# LAN8720.net
KiCad netlist of a schematic drawn in Altium Designer
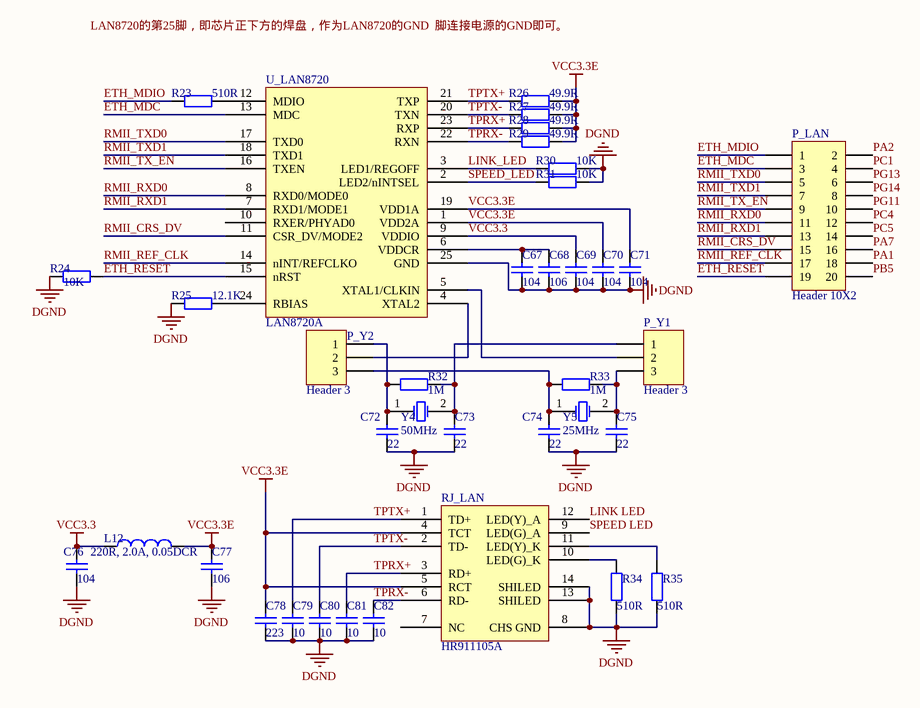
[diagram p0: LAN8720.SchDoc]

(export (version "E")
  (design (tool "Eeschema 10.0.6"))
  (components
    (comp (ref "C67")
      (value "104")
      (footprint "SMT-0603")
      (description "Capacitor")
      (fields (field (name "Comment") "Cap") (field (name "PUBLISHER") "Altium Limited"))
      (libsource (lib "Miscellaneous Devices") (part "Cap"))
    )
    (comp (ref "C68")
      (value "106")
      (footprint "SMT-0603")
      (description "Capacitor")
      (fields (field (name "Comment") "Cap") (field (name "PUBLISHER") "Altium Limited"))
      (libsource (lib "Miscellaneous Devices") (part "Cap"))
    )
    (comp (ref "C69")
      (value "104")
      (footprint "SMT-0603")
      (description "Capacitor")
      (fields (field (name "Comment") "Cap") (field (name "PUBLISHER") "Altium Limited"))
      (libsource (lib "Miscellaneous Devices") (part "Cap"))
    )
    (comp (ref "C70")
      (value "104")
      (footprint "SMT-0603")
      (description "Capacitor")
      (fields (field (name "Comment") "Cap") (field (name "PUBLISHER") "Altium Limited"))
      (libsource (lib "Miscellaneous Devices") (part "Cap"))
    )
    (comp (ref "C71")
      (value "104")
      (footprint "SMT-0603")
      (description "Capacitor")
      (fields (field (name "Comment") "Cap") (field (name "PUBLISHER") "Altium Limited"))
      (libsource (lib "Miscellaneous Devices") (part "Cap"))
    )
    (comp (ref "C72")
      (value "22")
      (footprint "SMT-0603")
      (description "Capacitor")
      (fields (field (name "Comment") "Cap") (field (name "PUBLISHER") "Altium Limited"))
      (libsource (lib "Miscellaneous Devices") (part "Cap"))
    )
    (comp (ref "C73")
      (value "22")
      (footprint "SMT-0603")
      (description "Capacitor")
      (fields (field (name "Comment") "Cap") (field (name "PUBLISHER") "Altium Limited"))
      (libsource (lib "Miscellaneous Devices") (part "Cap"))
    )
    (comp (ref "C74")
      (value "22")
      (footprint "SMT-0603")
      (description "Capacitor")
      (fields (field (name "Comment") "Cap") (field (name "PUBLISHER") "Altium Limited"))
      (libsource (lib "Miscellaneous Devices") (part "Cap"))
    )
    (comp (ref "C75")
      (value "22")
      (footprint "SMT-0603")
      (description "Capacitor")
      (fields (field (name "Comment") "Cap") (field (name "PUBLISHER") "Altium Limited"))
      (libsource (lib "Miscellaneous Devices") (part "Cap"))
    )
    (comp (ref "C76")
      (value "104")
      (footprint "SMT-0603")
      (description "Capacitor")
      (fields (field (name "Comment") "Cap") (field (name "PUBLISHER") "Altium Limited"))
      (libsource (lib "Miscellaneous Devices") (part "Cap"))
    )
    (comp (ref "C77")
      (value "106")
      (footprint "SMT-0603")
      (description "Capacitor")
      (fields (field (name "Comment") "Cap") (field (name "PUBLISHER") "Altium Limited"))
      (libsource (lib "Miscellaneous Devices") (part "Cap"))
    )
    (comp (ref "C78")
      (value "223")
      (footprint "SMT-0603")
      (description "Capacitor")
      (fields (field (name "Comment") "Cap") (field (name "PUBLISHER") "Altium Limited"))
      (libsource (lib "Miscellaneous Devices") (part "Cap"))
    )
    (comp (ref "C79")
      (value "10")
      (footprint "SMT-0603")
      (description "Capacitor")
      (fields (field (name "Comment") "Cap") (field (name "PUBLISHER") "Altium Limited"))
      (libsource (lib "Miscellaneous Devices") (part "Cap"))
    )
    (comp (ref "C80")
      (value "10")
      (footprint "SMT-0603")
      (description "Capacitor")
      (fields (field (name "Comment") "Cap") (field (name "PUBLISHER") "Altium Limited"))
      (libsource (lib "Miscellaneous Devices") (part "Cap"))
    )
    (comp (ref "C81")
      (value "10")
      (footprint "SMT-0603")
      (description "Capacitor")
      (fields (field (name "Comment") "Cap") (field (name "PUBLISHER") "Altium Limited"))
      (libsource (lib "Miscellaneous Devices") (part "Cap"))
    )
    (comp (ref "C82")
      (value "10")
      (footprint "SMT-0603")
      (description "Capacitor")
      (fields (field (name "Comment") "Cap") (field (name "PUBLISHER") "Altium Limited"))
      (libsource (lib "Miscellaneous Devices") (part "Cap"))
    )
    (comp (ref "L12")
      (value "220R, 2.0A, 0.05DCR")
      (footprint "SMT-0603")
      (description "Inductor")
      (fields (field (name "PUBLISHER") "Altium Limited"))
      (libsource (lib "Miscellaneous Devices") (part "Inductor"))
    )
    (comp (ref "P_LAN")
      (value "Header 10X2")
      (footprint "HDR2X10")
      (description "Header, 10-Pin, Dual row")
      (fields (field (name "PUBLISHER") "Altium Limited"))
      (libsource (lib "Miscellaneous Connectors") (part "Header 10X2"))
    )
    (comp (ref "P_Y1")
      (value "Header 3")
      (footprint "HDR1X3")
      (description "Header, 3-Pin")
      (fields (field (name "PUBLISHER") "Altium Limited"))
      (libsource (lib "") (part "Header 3_1"))
    )
    (comp (ref "P_Y2")
      (value "Header 3")
      (footprint "HDR1X3")
      (description "Header, 3-Pin")
      (fields (field (name "PUBLISHER") "Altium Limited"))
      (libsource (lib "Miscellaneous Connectors") (part "Header 3"))
    )
    (comp (ref "R23")
      (value "510R")
      (footprint "SMT-0603")
      (description "Resistor")
      (fields (field (name "Comment") "Res2") (field (name "PUBLISHER") "Altium Limited"))
      (libsource (lib "Miscellaneous Devices") (part "Res2"))
    )
    (comp (ref "R24")
      (value "10K")
      (footprint "SMT-0603")
      (description "Resistor")
      (fields (field (name "Comment") "Res2") (field (name "PUBLISHER") "Altium Limited"))
      (libsource (lib "Miscellaneous Devices") (part "Res2"))
    )
    (comp (ref "R25")
      (value "12.1K")
      (footprint "SMT-0603")
      (description "Resistor")
      (fields (field (name "Comment") "Res2") (field (name "PUBLISHER") "Altium Limited"))
      (libsource (lib "Miscellaneous Devices") (part "Res2"))
    )
    (comp (ref "R26")
      (value "49.9R")
      (footprint "SMT-0603")
      (description "Resistor")
      (fields (field (name "Comment") "Res2") (field (name "PUBLISHER") "Altium Limited"))
      (libsource (lib "Miscellaneous Devices") (part "Res2"))
    )
    (comp (ref "R27")
      (value "49.9R")
      (footprint "SMT-0603")
      (description "Resistor")
      (fields (field (name "Comment") "Res2") (field (name "PUBLISHER") "Altium Limited"))
      (libsource (lib "Miscellaneous Devices") (part "Res2"))
    )
    (comp (ref "R28")
      (value "49.9R")
      (footprint "SMT-0603")
      (description "Resistor")
      (fields (field (name "Comment") "Res2") (field (name "PUBLISHER") "Altium Limited"))
      (libsource (lib "Miscellaneous Devices") (part "Res2"))
    )
    (comp (ref "R29")
      (value "49.9R")
      (footprint "SMT-0603")
      (description "Resistor")
      (fields (field (name "Comment") "Res2") (field (name "PUBLISHER") "Altium Limited"))
      (libsource (lib "Miscellaneous Devices") (part "Res2"))
    )
    (comp (ref "R30")
      (value "10K")
      (footprint "SMT-0603")
      (description "Resistor")
      (fields (field (name "Comment") "Res2") (field (name "PUBLISHER") "Altium Limited"))
      (libsource (lib "Miscellaneous Devices") (part "Res2"))
    )
    (comp (ref "R31")
      (value "10K")
      (footprint "SMT-0603")
      (description "Resistor")
      (fields (field (name "Comment") "Res2") (field (name "PUBLISHER") "Altium Limited"))
      (libsource (lib "Miscellaneous Devices") (part "Res2"))
    )
    (comp (ref "R32")
      (value "1M")
      (footprint "SMT-0603")
      (description "Resistor")
      (fields (field (name "Comment") "Res2") (field (name "PUBLISHER") "Altium Limited"))
      (libsource (lib "Miscellaneous Devices") (part "Res2"))
    )
    (comp (ref "R33")
      (value "1M")
      (footprint "SMT-0603")
      (description "Resistor")
      (fields (field (name "Comment") "Res2") (field (name "PUBLISHER") "Altium Limited"))
      (libsource (lib "Miscellaneous Devices") (part "Res2"))
    )
    (comp (ref "R34")
      (value "510R")
      (footprint "SMT-0603")
      (description "Resistor")
      (fields (field (name "Comment") "Res2") (field (name "PUBLISHER") "Altium Limited"))
      (libsource (lib "") (part "Res2_1"))
    )
    (comp (ref "R35")
      (value "510R")
      (footprint "SMT-0603")
      (description "Resistor")
      (fields (field (name "Comment") "Res2") (field (name "PUBLISHER") "Altium Limited"))
      (libsource (lib "") (part "Res2_1"))
    )
    (comp (ref "RJ_LAN") (value "HR911105A") (footprint "RJ45-LED") (libsource (lib "STM_ALL") (part "RJ45")))
    (comp (ref "U_LAN8720")
      (value "LAN8720A")
      (footprint "QFN24_0.5")
      (libsource (lib "STM_ALL") (part "LAN8720A"))
    )
    (comp (ref "Y4")
      (value "50MHz")
      (footprint "D-CRYSTAL3X8")
      (description "Crystal Oscillator")
      (fields (field (name "PUBLISHER") "Altium Limited"))
      (libsource (lib "Miscellaneous Devices") (part "XTAL"))
    )
    (comp (ref "Y5")
      (value "25MHz")
      (footprint "D-CRYSTAL3X8")
      (description "Crystal Oscillator")
      (fields (field (name "PUBLISHER") "Altium Limited"))
      (libsource (lib "Miscellaneous Devices") (part "XTAL"))
    )
  )
  (nets
    (net (code "1") (name "/ETH_MDC") (class "Default")
      (node (ref "P_LAN") (pin "3") (pinfunction "3_3") (pintype "passive"))
      (node (ref "U_LAN8720") (pin "13") (pinfunction "MDC_13") (pintype "passive"))
    )
    (net (code "2") (name "/ETH_MDIO") (class "Default")
      (node (ref "P_LAN") (pin "1") (pinfunction "1_1") (pintype "passive"))
      (node (ref "R23") (pin "1") (pinfunction "1_1") (pintype "passive"))
    )
    (net (code "3") (name "/ETH_RESET") (class "Default")
      (node (ref "P_LAN") (pin "19") (pinfunction "19_19") (pintype "passive"))
      (node (ref "R24") (pin "2") (pinfunction "2_2") (pintype "passive"))
      (node (ref "U_LAN8720") (pin "15") (pinfunction "nRST_15") (pintype "passive"))
    )
    (net (code "5") (name "/LINK LED") (class "Default")
      (node (ref "RJ_LAN") (pin "12") (pinfunction "LED(Y)_A_12") (pintype "passive"))
    )
    (net (code "6") (name "/LINK_LED") (class "Default")
      (node (ref "R30") (pin "1") (pinfunction "1_1") (pintype "passive"))
      (node (ref "U_LAN8720") (pin "3") (pinfunction "LED1/REGOFF_3") (pintype "passive"))
    )
    (net (code "7") (name "/PA1") (class "Default")
      (node (ref "P_LAN") (pin "18") (pinfunction "18_18") (pintype "passive"))
    )
    (net (code "8") (name "/PA2") (class "Default")
      (node (ref "P_LAN") (pin "2") (pinfunction "2_2") (pintype "passive"))
    )
    (net (code "9") (name "/PA7") (class "Default")
      (node (ref "P_LAN") (pin "16") (pinfunction "16_16") (pintype "passive"))
    )
    (net (code "10") (name "/PB5") (class "Default")
      (node (ref "P_LAN") (pin "20") (pinfunction "20_20") (pintype "passive"))
    )
    (net (code "11") (name "/PC1") (class "Default")
      (node (ref "P_LAN") (pin "4") (pinfunction "4_4") (pintype "passive"))
    )
    (net (code "12") (name "/PC4") (class "Default")
      (node (ref "P_LAN") (pin "12") (pinfunction "12_12") (pintype "passive"))
    )
    (net (code "13") (name "/PC5") (class "Default")
      (node (ref "P_LAN") (pin "14") (pinfunction "14_14") (pintype "passive"))
    )
    (net (code "14") (name "/PG11") (class "Default")
      (node (ref "P_LAN") (pin "10") (pinfunction "10_10") (pintype "passive"))
    )
    (net (code "15") (name "/PG13") (class "Default")
      (node (ref "P_LAN") (pin "6") (pinfunction "6_6") (pintype "passive"))
    )
    (net (code "16") (name "/PG14") (class "Default")
      (node (ref "P_LAN") (pin "8") (pinfunction "8_8") (pintype "passive"))
    )
    (net (code "17") (name "/RMII_CRS_DV") (class "Default")
      (node (ref "P_LAN") (pin "15") (pinfunction "15_15") (pintype "passive"))
      (node (ref "U_LAN8720") (pin "11") (pinfunction "CSR_DV/MODE2_11") (pintype "passive"))
    )
    (net (code "18") (name "/RMII_REF_CLK") (class "Default")
      (node (ref "P_LAN") (pin "17") (pinfunction "17_17") (pintype "passive"))
      (node (ref "U_LAN8720") (pin "14") (pinfunction "nINT/REFCLKO_14") (pintype "passive"))
    )
    (net (code "19") (name "/RMII_RXD0") (class "Default")
      (node (ref "P_LAN") (pin "11") (pinfunction "11_11") (pintype "passive"))
      (node (ref "U_LAN8720") (pin "8") (pinfunction "RXD0/MODE0_8") (pintype "passive"))
    )
    (net (code "20") (name "/RMII_RXD1") (class "Default")
      (node (ref "P_LAN") (pin "13") (pinfunction "13_13") (pintype "passive"))
      (node (ref "U_LAN8720") (pin "7") (pinfunction "RXD1/MODE1_7") (pintype "passive"))
    )
    (net (code "21") (name "/RMII_TXD0") (class "Default")
      (node (ref "P_LAN") (pin "5") (pinfunction "5_5") (pintype "passive"))
      (node (ref "U_LAN8720") (pin "17") (pinfunction "TXD0_17") (pintype "passive"))
    )
    (net (code "22") (name "/RMII_TXD1") (class "Default")
      (node (ref "P_LAN") (pin "7") (pinfunction "7_7") (pintype "passive"))
      (node (ref "U_LAN8720") (pin "18") (pinfunction "TXD1_18") (pintype "passive"))
    )
    (net (code "23") (name "/RMII_TX_EN") (class "Default")
      (node (ref "P_LAN") (pin "9") (pinfunction "9_9") (pintype "passive"))
      (node (ref "U_LAN8720") (pin "16") (pinfunction "TXEN_16") (pintype "passive"))
    )
    (net (code "24") (name "/SPEED LED") (class "Default")
      (node (ref "RJ_LAN") (pin "9") (pinfunction "LED(G)_A_9") (pintype "passive"))
    )
    (net (code "25") (name "/SPEED_LED") (class "Default")
      (node (ref "R31") (pin "1") (pinfunction "1_1") (pintype "passive"))
      (node (ref "U_LAN8720") (pin "2") (pinfunction "LED2/nINTSEL_2") (pintype "passive"))
    )
    (net (code "26") (name "/TPRX+") (class "Default")
      (node (ref "C81") (pin "2") (pinfunction "2_2") (pintype "passive"))
      (node (ref "R28") (pin "1") (pinfunction "1_1") (pintype "passive"))
      (node (ref "RJ_LAN") (pin "3") (pinfunction "RD+_3") (pintype "passive"))
      (node (ref "U_LAN8720") (pin "23") (pinfunction "RXP_23") (pintype "passive"))
    )
    (net (code "27") (name "/TPRX-") (class "Default")
      (node (ref "C82") (pin "2") (pinfunction "2_2") (pintype "passive"))
      (node (ref "R29") (pin "1") (pinfunction "1_1") (pintype "passive"))
      (node (ref "RJ_LAN") (pin "6") (pinfunction "RD-_6") (pintype "passive"))
      (node (ref "U_LAN8720") (pin "22") (pinfunction "RXN_22") (pintype "passive"))
    )
    (net (code "28") (name "/TPTX+") (class "Default")
      (node (ref "C79") (pin "2") (pinfunction "2_2") (pintype "passive"))
      (node (ref "R26") (pin "1") (pinfunction "1_1") (pintype "passive"))
      (node (ref "RJ_LAN") (pin "1") (pinfunction "TD+_1") (pintype "passive"))
      (node (ref "U_LAN8720") (pin "21") (pinfunction "TXP_21") (pintype "passive"))
    )
    (net (code "29") (name "/TPTX-") (class "Default")
      (node (ref "C80") (pin "2") (pinfunction "2_2") (pintype "passive"))
      (node (ref "R27") (pin "1") (pinfunction "1_1") (pintype "passive"))
      (node (ref "RJ_LAN") (pin "2") (pinfunction "TD-_2") (pintype "passive"))
      (node (ref "U_LAN8720") (pin "20") (pinfunction "TXN_20") (pintype "passive"))
    )
    (net (code "30") (name "DGND") (class "Default")
      (node (ref "C67") (pin "1") (pinfunction "1_1") (pintype "passive"))
      (node (ref "C68") (pin "1") (pinfunction "1_1") (pintype "passive"))
      (node (ref "C69") (pin "1") (pinfunction "1_1") (pintype "passive"))
      (node (ref "C70") (pin "1") (pinfunction "1_1") (pintype "passive"))
      (node (ref "C71") (pin "1") (pinfunction "1_1") (pintype "passive"))
      (node (ref "C72") (pin "1") (pinfunction "1_1") (pintype "passive"))
      (node (ref "C73") (pin "1") (pinfunction "1_1") (pintype "passive"))
      (node (ref "C74") (pin "1") (pinfunction "1_1") (pintype "passive"))
      (node (ref "C75") (pin "1") (pinfunction "1_1") (pintype "passive"))
      (node (ref "C76") (pin "1") (pinfunction "1_1") (pintype "passive"))
      (node (ref "C77") (pin "1") (pinfunction "1_1") (pintype "passive"))
      (node (ref "C78") (pin "1") (pinfunction "1_1") (pintype "passive"))
      (node (ref "C79") (pin "1") (pinfunction "1_1") (pintype "passive"))
      (node (ref "C80") (pin "1") (pinfunction "1_1") (pintype "passive"))
      (node (ref "C81") (pin "1") (pinfunction "1_1") (pintype "passive"))
      (node (ref "C82") (pin "1") (pinfunction "1_1") (pintype "passive"))
      (node (ref "R24") (pin "1") (pinfunction "1_1") (pintype "passive"))
      (node (ref "R25") (pin "1") (pinfunction "1_1") (pintype "passive"))
      (node (ref "R30") (pin "2") (pinfunction "2_2") (pintype "passive"))
      (node (ref "R31") (pin "2") (pinfunction "2_2") (pintype "passive"))
      (node (ref "R34") (pin "1") (pinfunction "1_1") (pintype "passive"))
      (node (ref "R35") (pin "1") (pinfunction "1_1") (pintype "passive"))
      (node (ref "RJ_LAN") (pin "13") (pinfunction "SHILED_13") (pintype "passive"))
      (node (ref "RJ_LAN") (pin "14") (pinfunction "SHILED_14") (pintype "passive"))
      (node (ref "RJ_LAN") (pin "8") (pinfunction "CHS_GND_8") (pintype "passive"))
      (node (ref "U_LAN8720") (pin "25") (pinfunction "GND_25") (pintype "passive"))
    )
    (net (code "31") (name "Net-(RJ_LAN-LED(G)_K)") (class "Default")
      (node (ref "R34") (pin "2") (pinfunction "2_2") (pintype "passive"))
      (node (ref "RJ_LAN") (pin "10") (pinfunction "LED(G)_K_10") (pintype "passive"))
    )
    (net (code "32") (name "Net-(RJ_LAN-LED(Y)_K)") (class "Default")
      (node (ref "R35") (pin "2") (pinfunction "2_2") (pintype "passive"))
      (node (ref "RJ_LAN") (pin "11") (pinfunction "LED(Y)_K_11") (pintype "passive"))
    )
    (net (code "33") (name "Net-(U_LAN8720-MDIO)") (class "Default")
      (node (ref "R23") (pin "2") (pinfunction "2_2") (pintype "passive"))
      (node (ref "U_LAN8720") (pin "12") (pinfunction "MDIO_12") (pintype "passive"))
    )
    (net (code "34") (name "Net-(U_LAN8720-RBIAS)") (class "Default")
      (node (ref "R25") (pin "2") (pinfunction "2_2") (pintype "passive"))
      (node (ref "U_LAN8720") (pin "24") (pinfunction "RBIAS_24") (pintype "passive"))
    )
    (net (code "35") (name "Net-(U_LAN8720-VDDCR)") (class "Default")
      (node (ref "C67") (pin "2") (pinfunction "2_2") (pintype "passive"))
      (node (ref "C68") (pin "2") (pinfunction "2_2") (pintype "passive"))
      (node (ref "U_LAN8720") (pin "6") (pinfunction "VDDCR_6") (pintype "passive"))
    )
    (net (code "36") (name "Net-(U_LAN8720-XTAL1{slash}CLKIN)") (class "Default")
      (node (ref "P_Y1") (pin "2") (pinfunction "2_2") (pintype "passive"))
      (node (ref "U_LAN8720") (pin "5") (pinfunction "XTAL1/CLKIN_5") (pintype "passive"))
    )
    (net (code "37") (name "Net-(U_LAN8720-XTAL2)") (class "Default")
      (node (ref "P_Y2") (pin "2") (pinfunction "2_2") (pintype "passive"))
      (node (ref "U_LAN8720") (pin "4") (pinfunction "XTAL2_4") (pintype "passive"))
    )
    (net (code "38") (name "Net-(Y4-OSC1)") (class "Default")
      (node (ref "C72") (pin "2") (pinfunction "2_2") (pintype "passive"))
      (node (ref "P_Y2") (pin "1") (pinfunction "1_1") (pintype "passive"))
      (node (ref "R32") (pin "1") (pinfunction "1_1") (pintype "passive"))
      (node (ref "Y4") (pin "1") (pinfunction "OSC1_1") (pintype "passive"))
    )
    (net (code "39") (name "Net-(Y4-OSC2)") (class "Default")
      (node (ref "C73") (pin "2") (pinfunction "2_2") (pintype "passive"))
      (node (ref "P_Y1") (pin "1") (pinfunction "1_1") (pintype "passive"))
      (node (ref "R32") (pin "2") (pinfunction "2_2") (pintype "passive"))
      (node (ref "Y4") (pin "2") (pinfunction "OSC2_2") (pintype "passive"))
    )
    (net (code "40") (name "Net-(Y5-OSC1)") (class "Default")
      (node (ref "C74") (pin "2") (pinfunction "2_2") (pintype "passive"))
      (node (ref "P_Y2") (pin "3") (pinfunction "3_3") (pintype "passive"))
      (node (ref "R33") (pin "1") (pinfunction "1_1") (pintype "passive"))
      (node (ref "Y5") (pin "1") (pinfunction "OSC1_1") (pintype "passive"))
    )
    (net (code "41") (name "Net-(Y5-OSC2)") (class "Default")
      (node (ref "C75") (pin "2") (pinfunction "2_2") (pintype "passive"))
      (node (ref "P_Y1") (pin "3") (pinfunction "3_3") (pintype "passive"))
      (node (ref "R33") (pin "2") (pinfunction "2_2") (pintype "passive"))
      (node (ref "Y5") (pin "2") (pinfunction "OSC2_2") (pintype "passive"))
    )
    (net (code "42") (name "VCC3.3") (class "Default")
      (node (ref "C69") (pin "2") (pinfunction "2_2") (pintype "passive"))
      (node (ref "C76") (pin "2") (pinfunction "2_2") (pintype "passive"))
      (node (ref "L12") (pin "1") (pinfunction "1_1") (pintype "passive"))
      (node (ref "U_LAN8720") (pin "9") (pinfunction "VDDIO_9") (pintype "passive"))
    )
    (net (code "43") (name "VCC3.3E") (class "Default")
      (node (ref "C70") (pin "2") (pinfunction "2_2") (pintype "passive"))
      (node (ref "C71") (pin "2") (pinfunction "2_2") (pintype "passive"))
      (node (ref "C77") (pin "2") (pinfunction "2_2") (pintype "passive"))
      (node (ref "C78") (pin "2") (pinfunction "2_2") (pintype "passive"))
      (node (ref "L12") (pin "2") (pinfunction "2_2") (pintype "passive"))
      (node (ref "R26") (pin "2") (pinfunction "2_2") (pintype "passive"))
      (node (ref "R27") (pin "2") (pinfunction "2_2") (pintype "passive"))
      (node (ref "R28") (pin "2") (pinfunction "2_2") (pintype "passive"))
      (node (ref "R29") (pin "2") (pinfunction "2_2") (pintype "passive"))
      (node (ref "RJ_LAN") (pin "4") (pinfunction "TCT_4") (pintype "passive"))
      (node (ref "RJ_LAN") (pin "5") (pinfunction "RCT_5") (pintype "passive"))
      (node (ref "U_LAN8720") (pin "1") (pinfunction "VDD2A_1") (pintype "passive"))
      (node (ref "U_LAN8720") (pin "19") (pinfunction "VDD1A_19") (pintype "passive"))
    )
    (net (code "44") (name "unconnected-(RJ_LAN-NC-Pad7)") (class "Default")
      (node (ref "RJ_LAN") (pin "7") (pinfunction "NC_7") (pintype "passive"))
    )
    (net (code "45") (name "unconnected-(U_LAN8720-RXER{slash}PHYAD0-Pad10)") (class "Default")
      (node (ref "U_LAN8720") (pin "10") (pinfunction "RXER/PHYAD0_10") (pintype "passive"))
    )
  )
)
